# Calisma.net
KiCad netlist of a schematic drawn in Altium Designer
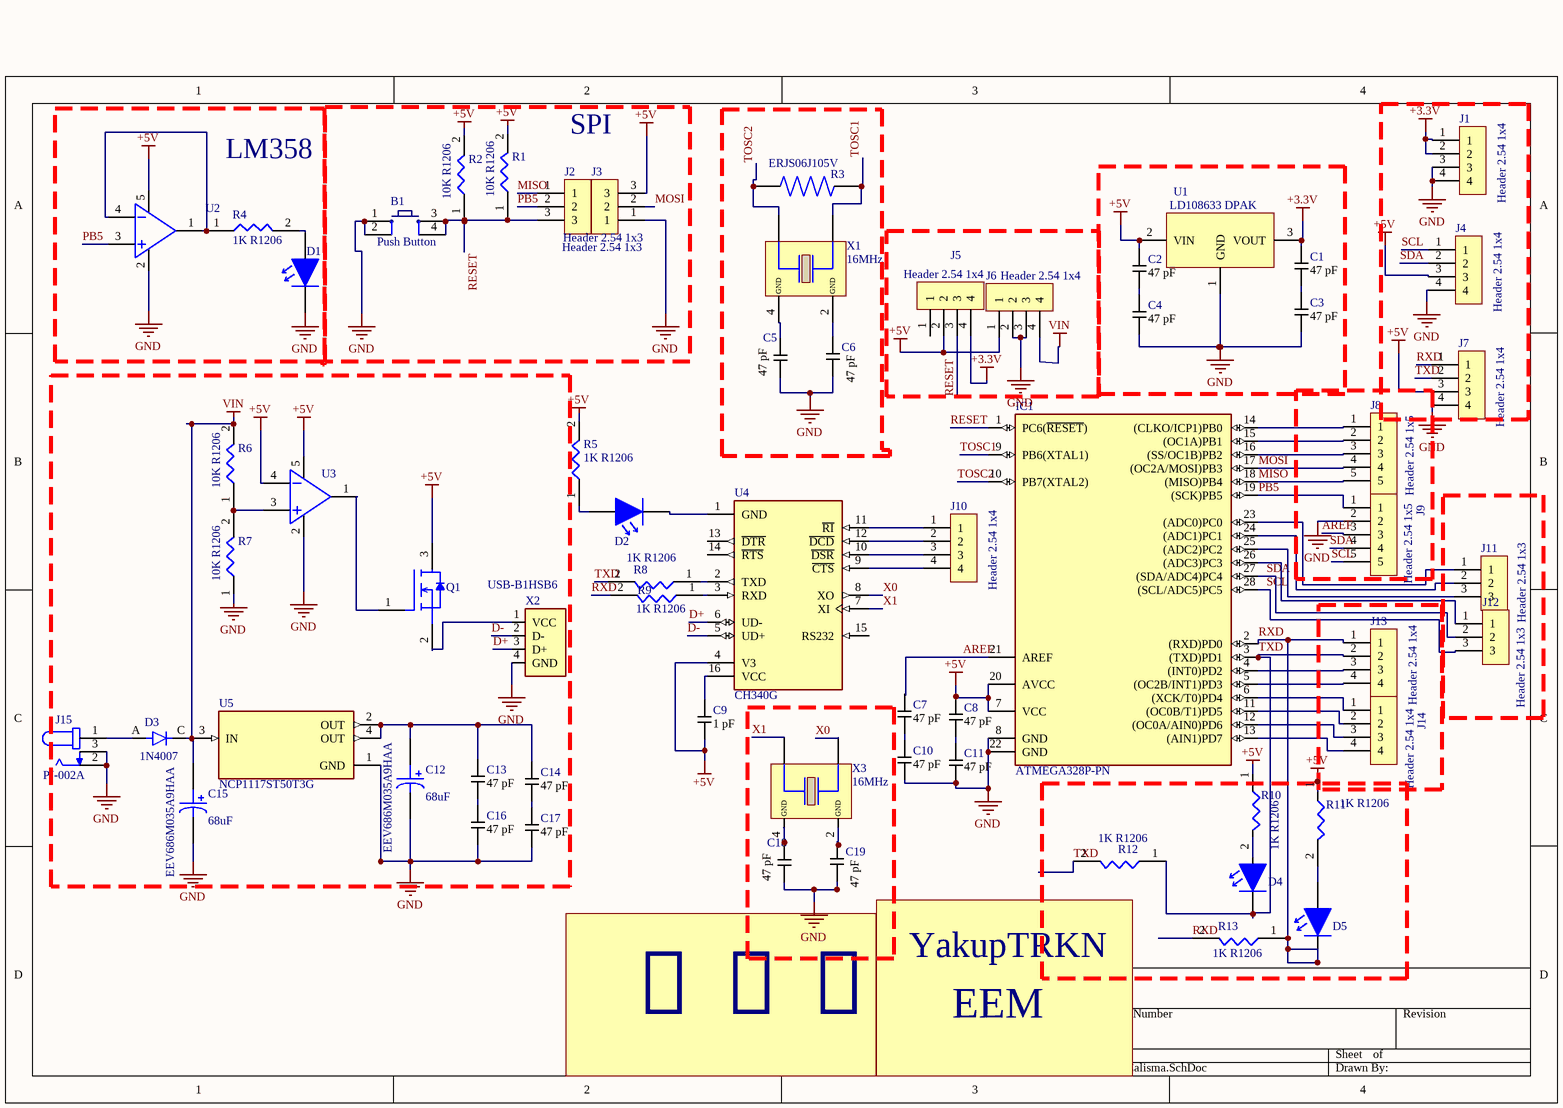
[diagram p0: Calisma.SchDoc]

(export (version "E")
  (design (tool "Eeschema 10.0.6"))
  (components
    (comp (ref "B1")
      (value "Push Button")
      (footprint "PUSB BUTTON-SMD")
      (description "Smd Push Button")
      (libsource (lib "Calisma") (part "Push Button"))
    )
    (comp (ref "C1")
      (value "CL10C470JB8NNNC")
      (footprint "SAMSUNG_CAP_0603_090")
      (description "CAP CER 47PF 50V C0G/NP0 0603")
      (fields (field (name "CAPACITANCE") "47 pF"))
      (libsource (lib "Calisma") (part "CL10C470JB8NNNC"))
    )
    (comp (ref "C2")
      (value "CL10C470JB8NNNC")
      (footprint "SAMSUNG_CAP_0603_090")
      (description "CAP CER 47PF 50V C0G/NP0 0603")
      (fields (field (name "CAPACITANCE") "47 pF"))
      (libsource (lib "Calisma") (part "CL10C470JB8NNNC"))
    )
    (comp (ref "C3")
      (value "CL10C470JB8NNNC")
      (footprint "SAMSUNG_CAP_0603_090")
      (description "CAP CER 47PF 50V C0G/NP0 0603")
      (fields (field (name "CAPACITANCE") "47 pF"))
      (libsource (lib "Calisma") (part "CL10C470JB8NNNC"))
    )
    (comp (ref "C4")
      (value "CL10C470JB8NNNC")
      (footprint "SAMSUNG_CAP_0603_090")
      (description "CAP CER 47PF 50V C0G/NP0 0603")
      (fields (field (name "CAPACITANCE") "47 pF"))
      (libsource (lib "Calisma") (part "CL10C470JB8NNNC"))
    )
    (comp (ref "C5")
      (value "CL10C470JB8NNNC")
      (footprint "SAMSUNG_CAP_0603_090")
      (description "CAP CER 47PF 50V C0G/NP0 0603")
      (fields (field (name "CAPACITANCE") "47 pF"))
      (libsource (lib "Calisma") (part "CL10C470JB8NNNC"))
    )
    (comp (ref "C6")
      (value "CL10C470JB8NNNC")
      (footprint "SAMSUNG_CAP_0603_090")
      (description "CAP CER 47PF 50V C0G/NP0 0603")
      (fields (field (name "CAPACITANCE") "47 pF"))
      (libsource (lib "Calisma") (part "CL10C470JB8NNNC"))
    )
    (comp (ref "C7")
      (value "CL10C470JB8NNNC")
      (footprint "SAMSUNG_CAP_0603_090")
      (description "CAP CER 47PF 50V C0G/NP0 0603")
      (fields (field (name "CAPACITANCE") "47 pF"))
      (libsource (lib "Calisma") (part "CL10C470JB8NNNC"))
    )
    (comp (ref "C8")
      (value "CL10C470JB8NNNC")
      (footprint "SAMSUNG_CAP_0603_090")
      (description "CAP CER 47PF 50V C0G/NP0 0603")
      (fields (field (name "CAPACITANCE") "47 pF"))
      (libsource (lib "Calisma") (part "CL10C470JB8NNNC"))
    )
    (comp (ref "C9")
      (value "CL10C010BB8NNNC")
      (footprint "SAMSUNG_CAP_0603_090")
      (description "CAP CER 1PF 50V C0G/NP0 0603")
      (fields (field (name "CAPACITANCE") "1 pF"))
      (libsource (lib "Calisma") (part "CL10C010BB8NNNC"))
    )
    (comp (ref "C10")
      (value "CL10C470JB8NNNC")
      (footprint "SAMSUNG_CAP_0603_090")
      (description "CAP CER 47PF 50V C0G/NP0 0603")
      (fields (field (name "CAPACITANCE") "47 pF"))
      (libsource (lib "Calisma") (part "CL10C470JB8NNNC"))
    )
    (comp (ref "C11")
      (value "CL10C470JB8NNNC")
      (footprint "SAMSUNG_CAP_0603_090")
      (description "CAP CER 47PF 50V C0G/NP0 0603")
      (fields (field (name "CAPACITANCE") "47 pF"))
      (libsource (lib "Calisma") (part "CL10C470JB8NNNC"))
    )
    (comp (ref "C12")
      (value "EEV686M035A9HAA")
      (footprint "CAP_EEVseries")
      (description "Cap Aluminum Lytic 68uF 35V 20% (6.3 X 7.7mm) SMD 280mA 2000h 105C T/R")
      (fields
        (field (name "MANUFACTURER") "KEMET")
        (field (name "TOLERANCE") "20%")
        (field (name "CAPACITANCE") "68uF")
      )
      (libsource (lib "Calisma") (part "CAP ALU 68uF"))
    )
    (comp (ref "C13")
      (value "CL10C470JB8NNNC")
      (footprint "SAMSUNG_CAP_0603_090")
      (description "CAP CER 47PF 50V C0G/NP0 0603")
      (fields (field (name "CAPACITANCE") "47 pF"))
      (libsource (lib "Calisma") (part "CL10C470JB8NNNC"))
    )
    (comp (ref "C14")
      (value "CL10C470JB8NNNC")
      (footprint "SAMSUNG_CAP_0603_090")
      (description "CAP CER 47PF 50V C0G/NP0 0603")
      (fields (field (name "CAPACITANCE") "47 pF"))
      (libsource (lib "Calisma") (part "CL10C470JB8NNNC"))
    )
    (comp (ref "C15")
      (value "EEV686M035A9HAA")
      (footprint "CAP_EEVseries")
      (description "Cap Aluminum Lytic 68uF 35V 20% (6.3 X 7.7mm) SMD 280mA 2000h 105C T/R")
      (fields
        (field (name "MANUFACTURER") "KEMET")
        (field (name "TOLERANCE") "20%")
        (field (name "CAPACITANCE") "68uF")
      )
      (libsource (lib "Calisma") (part "CAP ALU 68uF"))
    )
    (comp (ref "C16")
      (value "CL10C470JB8NNNC")
      (footprint "SAMSUNG_CAP_0603_090")
      (description "CAP CER 47PF 50V C0G/NP0 0603")
      (fields (field (name "CAPACITANCE") "47 pF"))
      (libsource (lib "Calisma") (part "CL10C470JB8NNNC"))
    )
    (comp (ref "C17")
      (value "CL10C470JB8NNNC")
      (footprint "SAMSUNG_CAP_0603_090")
      (description "CAP CER 47PF 50V C0G/NP0 0603")
      (fields (field (name "CAPACITANCE") "47 pF"))
      (libsource (lib "Calisma") (part "CL10C470JB8NNNC"))
    )
    (comp (ref "C18")
      (value "CL10C470JB8NNNC")
      (footprint "SAMSUNG_CAP_0603_090")
      (description "CAP CER 47PF 50V C0G/NP0 0603")
      (fields (field (name "CAPACITANCE") "47 pF"))
      (libsource (lib "Calisma") (part "CL10C470JB8NNNC"))
    )
    (comp (ref "C19")
      (value "CL10C470JB8NNNC")
      (footprint "SAMSUNG_CAP_0603_090")
      (description "CAP CER 47PF 50V C0G/NP0 0603")
      (fields (field (name "CAPACITANCE") "47 pF"))
      (libsource (lib "Calisma") (part "CL10C470JB8NNNC"))
    )
    (comp (ref "D1")
      (value "LH R974-LP-1")
      (footprint "LED_RED_0805")
      (description "LED Uni-Color Hyper Red 660nm 2-Pin Chip 0805(2012Metric) T/R")
      (fields (field (name "MANUFACTURER") "Osram Opto") (field (name "DESIGNED BY") "BERK"))
      (libsource (lib "Calisma") (part "LED RED 0805"))
    )
    (comp (ref "D2")
      (value "LTST-C171GKT")
      (footprint "LED_GREEN_0805")
      (description "Green 0805 130 º Min 5 mcd Typical 12 mcd Water Clear Lens SMT LED")
      (fields (field (name "MANUFACTURER") "Vishay Lite-On") (field (name "DESIGNED BY") "BERK"))
      (libsource (lib "Calisma") (part "LED GREEN 0805"))
    )
    (comp (ref "D3")
      (value "1N4007")
      (footprint "1N4007:DIOAD1060W80L520D270")
      (description "Diode Switching 1KV 1A 2-Pin DO-41")
      (fields (field (name "MF") "{'manufacturer': u'ON Semiconductor'}"))
      (libsource (lib "Calisma") (part "1N4007"))
    )
    (comp (ref "D4")
      (value "LTST-C171GKT")
      (footprint "LED_GREEN_0805")
      (description "Green 0805 130 º Min 5 mcd Typical 12 mcd Water Clear Lens SMT LED")
      (fields (field (name "MANUFACTURER") "Vishay Lite-On") (field (name "DESIGNED BY") "BERK"))
      (libsource (lib "Calisma") (part "LED GREEN 0805"))
    )
    (comp (ref "D5")
      (value "LTST-C171GKT")
      (footprint "LED_GREEN_0805")
      (description "Green 0805 130 º Min 5 mcd Typical 12 mcd Water Clear Lens SMT LED")
      (fields (field (name "MANUFACTURER") "Vishay Lite-On") (field (name "DESIGNED BY") "BERK"))
      (libsource (lib "Calisma") (part "LED GREEN 0805"))
    )
    (comp (ref "IC1")
      (value "ATMEGA328P-PN")
      (footprint "ATMEGA328P-PN:DIL28")
      (description "Atmel ATmega48/88/168/328 AVR Microcontroller")
      (fields (field (name "MF") "{'manufacturer': u'Microchip'}"))
      (libsource (lib "Calisma") (part "ATMEGA328P-PN"))
    )
    (comp (ref "J1")
      (value "Header 2.54 1x4")
      (footprint "Header 2.54 1x4")
      (libsource (lib "Calisma") (part "Header 2.54 1x4"))
    )
    (comp (ref "J2")
      (value "Header 2.54 1x3")
      (footprint "Header 2.54 1x3")
      (libsource (lib "") (part "Header 2.54 1x3_1"))
    )
    (comp (ref "J3")
      (value "Header 2.54 1x3")
      (footprint "Header 2.54 1x3")
      (libsource (lib "Calisma") (part "Header 2.54 1x3"))
    )
    (comp (ref "J4")
      (value "Header 2.54 1x4")
      (footprint "Header 2.54 1x4")
      (libsource (lib "Calisma") (part "Header 2.54 1x4"))
    )
    (comp (ref "J5")
      (value "Header 2.54 1x4")
      (footprint "Header 2.54 1x4")
      (libsource (lib "") (part "Header 2.54 1x4_1"))
    )
    (comp (ref "J6")
      (value "Header 2.54 1x4")
      (footprint "Header 2.54 1x4")
      (libsource (lib "") (part "Header 2.54 1x4_1"))
    )
    (comp (ref "J7")
      (value "Header 2.54 1x4")
      (footprint "Header 2.54 1x4")
      (libsource (lib "Calisma") (part "Header 2.54 1x4"))
    )
    (comp (ref "J8")
      (value "Header 2.54 1x5")
      (footprint "Header 2.54 1x5")
      (libsource (lib "Calisma") (part "Header 2.54 1x5"))
    )
    (comp (ref "J9")
      (value "Header 2.54 1x5")
      (footprint "Header 2.54 1x5")
      (libsource (lib "Calisma") (part "Header 2.54 1x5"))
    )
    (comp (ref "J10")
      (value "Header 2.54 1x4")
      (footprint "Header 2.54 1x4")
      (libsource (lib "Calisma") (part "Header 2.54 1x4"))
    )
    (comp (ref "J11")
      (value "Header 2.54 1x3")
      (footprint "Header 2.54 1x3")
      (libsource (lib "") (part "Header 2.54 1x3_1"))
    )
    (comp (ref "J12")
      (value "Header 2.54 1x3")
      (footprint "Header 2.54 1x3")
      (libsource (lib "") (part "Header 2.54 1x3_1"))
    )
    (comp (ref "J13")
      (value "Header 2.54 1x4")
      (footprint "Header 2.54 1x4")
      (libsource (lib "Calisma") (part "Header 2.54 1x4"))
    )
    (comp (ref "J14")
      (value "Header 2.54 1x4")
      (footprint "Header 2.54 1x4")
      (libsource (lib "Calisma") (part "Header 2.54 1x4"))
    )
    (comp (ref "J15")
      (value "PJ-002A")
      (footprint "PJ-002A:CUI_PJ-002A")
      (description "2.0 mm Center Pin, 2.5 A, Right Angle, Through Hole, Dc Power Jack Connector")
      (fields (field (name "MF") "{'manufacturer': u'CUI Devices'}"))
      (libsource (lib "Calisma") (part "PJ-002A"))
    )
    (comp (ref "Q1")
      (value "SSM3K357R,LF")
      (footprint "SOT-23F")
      (description "X34 SMALL LOW ON RESISTANCE MOSF")
      (fields (field (name "MANUFACTURER") "Toshiba") (field (name "DESIGNED BY") "BERK"))
      (libsource (lib "Calisma") (part "SSM3K357R,LF"))
    )
    (comp (ref "R1")
      (value "10K R1206")
      (footprint "R1206 Resıstor")
      (libsource (lib "Calisma") (part "10K R1206"))
    )
    (comp (ref "R2")
      (value "10K R1206")
      (footprint "R1206 Resıstor")
      (libsource (lib "Calisma") (part "10K R1206"))
    )
    (comp (ref "R3")
      (value "ERJS06J105V")
      (footprint "ERJ-S06J105V:RES_ERJS06J105V")
      (fields (field (name "MF") "{'manufacturer': u'Panasonic'}"))
      (libsource (lib "Calisma") (part "ERJS06J105V"))
    )
    (comp (ref "R4")
      (value "1K R1206")
      (footprint "R1206 Resıstor")
      (libsource (lib "Calisma") (part "1K R1206"))
    )
    (comp (ref "R5")
      (value "1K R1206")
      (footprint "R1206 Resıstor")
      (libsource (lib "Calisma") (part "1K R1206"))
    )
    (comp (ref "R6")
      (value "10K R1206")
      (footprint "R1206 Resıstor")
      (libsource (lib "Calisma") (part "10K R1206"))
    )
    (comp (ref "R7")
      (value "10K R1206")
      (footprint "R1206 Resıstor")
      (libsource (lib "Calisma") (part "10K R1206"))
    )
    (comp (ref "R8")
      (value "1K R1206")
      (footprint "R1206 Resıstor")
      (libsource (lib "Calisma") (part "1K R1206"))
    )
    (comp (ref "R9")
      (value "1K R1206")
      (footprint "R1206 Resıstor")
      (libsource (lib "Calisma") (part "1K R1206"))
    )
    (comp (ref "R10")
      (value "1K R1206")
      (footprint "R1206 Resıstor")
      (libsource (lib "Calisma") (part "1K R1206"))
    )
    (comp (ref "R11")
      (value "1K R1206")
      (footprint "R1206 Resıstor")
      (libsource (lib "Calisma") (part "1K R1206"))
    )
    (comp (ref "R12")
      (value "1K R1206")
      (footprint "R1206 Resıstor")
      (libsource (lib "Calisma") (part "1K R1206"))
    )
    (comp (ref "R13")
      (value "1K R1206")
      (footprint "R1206 Resıstor")
      (libsource (lib "Calisma") (part "1K R1206"))
    )
    (comp (ref "U1")
      (value "LD108633 DPAK")
      (footprint "DPAK228P972X230-3N")
      (description "LD1086 3.3V REGULATOR")
      (libsource (lib "Calisma") (part "LD108633 DPAK"))
    )
    (comp (ref "U2")
      (value "OPA314AIDBVR")
      (footprint "SOT23-5")
      (description "Op Amp OPA314")
      (fields (field (name "MANUFACTURER") "Texas Instruments") (field (name "DESIGNED BY") "BERK"))
      (libsource (lib "Calisma") (part "OPA314"))
    )
    (comp (ref "U3")
      (value "OPA314AIDBVR")
      (footprint "SOT23-5")
      (description "Op Amp OPA314")
      (fields (field (name "MANUFACTURER") "Texas Instruments") (field (name "DESIGNED BY") "BERK"))
      (libsource (lib "Calisma") (part "OPA314"))
    )
    (comp (ref "U4")
      (value "CH340G")
      (footprint "Ch340G:SOIC127P600X180-16N")
      (fields (field (name "MF") "{'manufacturer': u'WCH'}"))
      (libsource (lib "Calisma") (part "CH340G"))
    )
    (comp (ref "U5")
      (value "NCP1117ST50T3G")
      (footprint "NCP1117ST50T3G:SOT230P700X180-4N")
      (description "1.0 A Low-Dropout Positive ,Fixed and Adjustable,Voltage Regulators")
      (fields (field (name "MF") "{'manufacturer': u'ON Semiconductor'}"))
      (libsource (lib "Calisma") (part "NCP1117ST50T3G"))
    )
    (comp (ref "X1")
      (value "ECS-160-20-30B-TR")
      (footprint "ECS")
      (description "CRYSTAL 16.0000MHZ 20PF SMD")
      (fields
        (field (name "MANUFACTURER") "ECS International")
        (field (name "TOLERANCE") "50ppm")
        (field (name "FREQUENCY") "16MHz")
        (field (name "DESIGNED BY") "BERK")
      )
      (libsource (lib "Calisma") (part "CRYSTAL 16MHz"))
    )
    (comp (ref "X2")
      (value "USB-B1HSB6")
      (footprint "USB-B1HSB6:OST_USB-B1HSB6")
      (description "Conn Usb Type b r/a Black")
      (fields (field (name "MF") "{'manufacturer': u'On Shore'}"))
      (libsource (lib "Calisma") (part "USB-B1HSB6"))
    )
    (comp (ref "X3")
      (value "ECS-160-20-30B-TR")
      (footprint "ECS")
      (description "CRYSTAL 16.0000MHZ 20PF SMD")
      (fields
        (field (name "MANUFACTURER") "ECS International")
        (field (name "TOLERANCE") "50ppm")
        (field (name "FREQUENCY") "16MHz")
        (field (name "DESIGNED BY") "BERK")
      )
      (libsource (lib "Calisma") (part "CRYSTAL 16MHz"))
    )
  )
  (nets
    (net (code "1") (name "+3.3V") (class "Default")
      (node (ref "C1") (pin "2") (pinfunction "2_2") (pintype "passive"))
      (node (ref "J1") (pin "1") (pinfunction "1_1") (pintype "passive"))
      (node (ref "J1") (pin "2") (pinfunction "2_2") (pintype "passive"))
      (node (ref "J5") (pin "4") (pinfunction "4_4") (pintype "passive"))
      (node (ref "U1") (pin "3") (pinfunction "VOUT_3") (pintype "passive"))
    )
    (net (code "2") (name "+5V") (class "Default")
      (node (ref "C2") (pin "2") (pinfunction "2_2") (pintype "passive"))
      (node (ref "C8") (pin "2") (pinfunction "2_2") (pintype "passive"))
      (node (ref "C9") (pin "1") (pinfunction "1_1") (pintype "passive"))
      (node (ref "IC1") (pin "20") (pinfunction "AVCC_20") (pintype "power_in"))
      (node (ref "IC1") (pin "7") (pinfunction "VCC_7") (pintype "power_in"))
      (node (ref "J3") (pin "3") (pinfunction "3_3") (pintype "passive"))
      (node (ref "J4") (pin "3") (pinfunction "3_3") (pintype "passive"))
      (node (ref "J5") (pin "2") (pinfunction "2_2") (pintype "passive"))
      (node (ref "J6") (pin "1") (pinfunction "1_1") (pintype "passive"))
      (node (ref "J7") (pin "3") (pinfunction "3_3") (pintype "passive"))
      (node (ref "Q1") (pin "3") (pinfunction "D_3") (pintype "passive"))
      (node (ref "R1") (pin "2") (pinfunction "2_2") (pintype "passive"))
      (node (ref "R10") (pin "1") (pinfunction "1_1") (pintype "passive"))
      (node (ref "R11") (pin "1") (pinfunction "1_1") (pintype "passive"))
      (node (ref "R2") (pin "2") (pinfunction "2_2") (pintype "passive"))
      (node (ref "R5") (pin "2") (pinfunction "2_2") (pintype "passive"))
      (node (ref "U1") (pin "2") (pinfunction "VIN_2") (pintype "passive"))
      (node (ref "U2") (pin "5") (pinfunction "5_5") (pintype "passive"))
      (node (ref "U3") (pin "4") (pinfunction "4_4") (pintype "passive"))
      (node (ref "U3") (pin "5") (pinfunction "5_5") (pintype "passive"))
      (node (ref "U4") (pin "4") (pinfunction "V3_4") (pintype "power_in"))
    )
    (net (code "3") (name "/AREF") (class "Default")
      (node (ref "IC1") (pin "21") (pinfunction "AREF_21") (pintype "passive"))
      (node (ref "J9") (pin "3") (pinfunction "3_3") (pintype "passive"))
    )
    (net (code "4") (name "/D+") (class "Default")
      (node (ref "U4") (pin "6") (pinfunction "UD-_6") (pintype "bidirectional"))
      (node (ref "X2") (pin "3") (pinfunction "D+_3") (pintype "bidirectional"))
    )
    (net (code "5") (name "/D-") (class "Default")
      (node (ref "U4") (pin "5") (pinfunction "UD+_5") (pintype "bidirectional"))
      (node (ref "X2") (pin "2") (pinfunction "D-_2") (pintype "bidirectional"))
    )
    (net (code "6") (name "/MISO") (class "Default")
      (node (ref "IC1") (pin "18") (pinfunction "(MISO)PB4_18") (pintype "bidirectional"))
      (node (ref "J2") (pin "1") (pinfunction "1_1") (pintype "passive"))
      (node (ref "J8") (pin "5") (pinfunction "5_5") (pintype "passive"))
    )
    (net (code "7") (name "/MOSI") (class "Default")
      (node (ref "IC1") (pin "17") (pinfunction "(OC2A/MOSI)PB3_17") (pintype "bidirectional"))
      (node (ref "J3") (pin "2") (pinfunction "2_2") (pintype "passive"))
      (node (ref "J8") (pin "4") (pinfunction "4_4") (pintype "passive"))
    )
    (net (code "8") (name "/PB5") (class "Default")
      (node (ref "IC1") (pin "19") (pinfunction "(SCK)PB5_19") (pintype "bidirectional"))
      (node (ref "J2") (pin "2") (pinfunction "2_2") (pintype "passive"))
      (node (ref "J9") (pin "1") (pinfunction "1_1") (pintype "passive"))
      (node (ref "U2") (pin "3") (pinfunction "3_3") (pintype "passive"))
    )
    (net (code "9") (name "/RESET") (class "Default")
      (node (ref "B1") (pin "3") (pinfunction "3_3") (pintype "passive"))
      (node (ref "B1") (pin "4") (pinfunction "4_4") (pintype "passive"))
      (node (ref "IC1") (pin "1") (pinfunction "PC6(~{RESET})_1") (pintype "bidirectional"))
      (node (ref "J2") (pin "3") (pinfunction "3_3") (pintype "passive"))
      (node (ref "J5") (pin "3") (pinfunction "3_3") (pintype "passive"))
      (node (ref "R1") (pin "1") (pinfunction "1_1") (pintype "passive"))
      (node (ref "R2") (pin "1") (pinfunction "1_1") (pintype "passive"))
    )
    (net (code "10") (name "/RXD") (class "Default")
      (node (ref "D5") (pin "1") (pinfunction "1_1") (pintype "power_in"))
      (node (ref "IC1") (pin "2") (pinfunction "(RXD)PD0_2") (pintype "bidirectional"))
      (node (ref "J13") (pin "1") (pinfunction "1_1") (pintype "passive"))
      (node (ref "J7") (pin "1") (pinfunction "1_1") (pintype "passive"))
      (node (ref "R13") (pin "1") (pinfunction "1_1") (pintype "passive"))
      (node (ref "R13") (pin "2") (pinfunction "2_2") (pintype "passive"))
      (node (ref "R9") (pin "2") (pinfunction "2_2") (pintype "passive"))
    )
    (net (code "11") (name "/SCL") (class "Default")
      (node (ref "IC1") (pin "28") (pinfunction "(SCL/ADC5)PC5_28") (pintype "bidirectional"))
      (node (ref "J12") (pin "3") (pinfunction "3_3") (pintype "passive"))
      (node (ref "J4") (pin "1") (pinfunction "1_1") (pintype "passive"))
      (node (ref "J9") (pin "5") (pinfunction "5_5") (pintype "passive"))
    )
    (net (code "12") (name "/SDA") (class "Default")
      (node (ref "IC1") (pin "27") (pinfunction "(SDA/ADC4)PC4_27") (pintype "bidirectional"))
      (node (ref "J12") (pin "2") (pinfunction "2_2") (pintype "passive"))
      (node (ref "J4") (pin "2") (pinfunction "2_2") (pintype "passive"))
      (node (ref "J9") (pin "4") (pinfunction "4_4") (pintype "passive"))
    )
    (net (code "13") (name "/TOSC1") (class "Default")
      (node (ref "IC1") (pin "9") (pinfunction "PB6(XTAL1)_9") (pintype "bidirectional"))
      (node (ref "R3") (pin "2") (pinfunction "2_2") (pintype "passive"))
      (node (ref "X1") (pin "1") (pinfunction "1_1") (pintype "passive"))
    )
    (net (code "14") (name "/TOSC2") (class "Default")
      (node (ref "IC1") (pin "10") (pinfunction "PB7(XTAL2)_10") (pintype "bidirectional"))
      (node (ref "R3") (pin "1") (pinfunction "1_1") (pintype "passive"))
      (node (ref "X1") (pin "3") (pinfunction "3_3") (pintype "passive"))
    )
    (net (code "15") (name "/TXD") (class "Default")
      (node (ref "D4") (pin "1") (pinfunction "1_1") (pintype "power_in"))
      (node (ref "IC1") (pin "3") (pinfunction "(TXD)PD1_3") (pintype "bidirectional"))
      (node (ref "J13") (pin "2") (pinfunction "2_2") (pintype "passive"))
      (node (ref "J7") (pin "2") (pinfunction "2_2") (pintype "passive"))
      (node (ref "R12") (pin "1") (pinfunction "1_1") (pintype "passive"))
      (node (ref "R12") (pin "2") (pinfunction "2_2") (pintype "passive"))
      (node (ref "R8") (pin "2") (pinfunction "2_2") (pintype "passive"))
    )
    (net (code "16") (name "/X0") (class "Default")
      (node (ref "U4") (pin "8") (pinfunction "XO_8") (pintype "output"))
      (node (ref "X3") (pin "1") (pinfunction "1_1") (pintype "passive"))
    )
    (net (code "17") (name "/X1") (class "Default")
      (node (ref "U4") (pin "7") (pinfunction "XI_7") (pintype "input"))
      (node (ref "X3") (pin "3") (pinfunction "3_3") (pintype "passive"))
    )
    (net (code "18") (name "GND") (class "Default")
      (node (ref "B1") (pin "1") (pinfunction "1_1") (pintype "passive"))
      (node (ref "B1") (pin "2") (pinfunction "2_2") (pintype "passive"))
      (node (ref "C10") (pin "1") (pinfunction "1_1") (pintype "passive"))
      (node (ref "C11") (pin "1") (pinfunction "1_1") (pintype "passive"))
      (node (ref "C12") (pin "2") (pinfunction "2_2") (pintype "passive"))
      (node (ref "C15") (pin "2") (pinfunction "2_2") (pintype "passive"))
      (node (ref "C16") (pin "1") (pinfunction "1_1") (pintype "passive"))
      (node (ref "C17") (pin "1") (pinfunction "1_1") (pintype "passive"))
      (node (ref "C18") (pin "1") (pinfunction "1_1") (pintype "passive"))
      (node (ref "C19") (pin "1") (pinfunction "1_1") (pintype "passive"))
      (node (ref "C3") (pin "1") (pinfunction "1_1") (pintype "passive"))
      (node (ref "C4") (pin "1") (pinfunction "1_1") (pintype "passive"))
      (node (ref "C5") (pin "1") (pinfunction "1_1") (pintype "passive"))
      (node (ref "C6") (pin "1") (pinfunction "1_1") (pintype "passive"))
      (node (ref "D1") (pin "1") (pinfunction "1_1") (pintype "power_in"))
      (node (ref "IC1") (pin "22") (pinfunction "GND_22") (pintype "power_in"))
      (node (ref "IC1") (pin "8") (pinfunction "GND_8") (pintype "power_in"))
      (node (ref "J1") (pin "3") (pinfunction "3_3") (pintype "passive"))
      (node (ref "J1") (pin "4") (pinfunction "4_4") (pintype "passive"))
      (node (ref "J15") (pin "2") (pinfunction "2_2") (pintype "passive"))
      (node (ref "J15") (pin "3") (pinfunction "3_3") (pintype "passive"))
      (node (ref "J3") (pin "1") (pinfunction "1_1") (pintype "passive"))
      (node (ref "J4") (pin "4") (pinfunction "4_4") (pintype "passive"))
      (node (ref "J6") (pin "2") (pinfunction "2_2") (pintype "passive"))
      (node (ref "J6") (pin "3") (pinfunction "3_3") (pintype "passive"))
      (node (ref "J7") (pin "4") (pinfunction "4_4") (pintype "passive"))
      (node (ref "J9") (pin "2") (pinfunction "2_2") (pintype "passive"))
      (node (ref "R7") (pin "1") (pinfunction "1_1") (pintype "passive"))
      (node (ref "U1") (pin "1") (pinfunction "GND_1") (pintype "passive"))
      (node (ref "U2") (pin "2") (pinfunction "2_2") (pintype "passive"))
      (node (ref "U3") (pin "2") (pinfunction "2_2") (pintype "passive"))
      (node (ref "U5") (pin "1") (pinfunction "GND_1") (pintype "power_in"))
      (node (ref "X2") (pin "4") (pinfunction "GND_4") (pintype "power_in"))
    )
    (net (code "19") (name "Net-(C1-Pad1)") (class "Default")
      (node (ref "C1") (pin "1") (pinfunction "1_1") (pintype "passive"))
      (node (ref "C3") (pin "2") (pinfunction "2_2") (pintype "passive"))
    )
    (net (code "20") (name "Net-(C2-Pad1)") (class "Default")
      (node (ref "C2") (pin "1") (pinfunction "1_1") (pintype "passive"))
      (node (ref "C4") (pin "2") (pinfunction "2_2") (pintype "passive"))
    )
    (net (code "21") (name "Net-(C5-Pad2)") (class "Default")
      (node (ref "C5") (pin "2") (pinfunction "2_2") (pintype "passive"))
      (node (ref "X1") (pin "4") (pinfunction "GND_4") (pintype "passive"))
    )
    (net (code "22") (name "Net-(C6-Pad2)") (class "Default")
      (node (ref "C6") (pin "2") (pinfunction "2_2") (pintype "passive"))
      (node (ref "X1") (pin "2") (pinfunction "GND_2") (pintype "passive"))
    )
    (net (code "23") (name "Net-(C10-Pad2)") (class "Default")
      (node (ref "C10") (pin "2") (pinfunction "2_2") (pintype "passive"))
      (node (ref "C7") (pin "1") (pinfunction "1_1") (pintype "passive"))
    )
    (net (code "24") (name "Net-(C11-Pad2)") (class "Default")
      (node (ref "C11") (pin "2") (pinfunction "2_2") (pintype "passive"))
      (node (ref "C8") (pin "1") (pinfunction "1_1") (pintype "passive"))
    )
    (net (code "25") (name "Net-(C12-Pad1)") (class "Default")
      (node (ref "C12") (pin "1") (pinfunction "1_1") (pintype "passive"))
      (node (ref "C13") (pin "2") (pinfunction "2_2") (pintype "passive"))
      (node (ref "C14") (pin "2") (pinfunction "2_2") (pintype "passive"))
      (node (ref "U5") (pin "2") (pinfunction "OUT_2") (pintype "output"))
      (node (ref "U5") (pin "4") (pinfunction "OUT_4") (pintype "output"))
    )
    (net (code "26") (name "Net-(C13-Pad1)") (class "Default")
      (node (ref "C13") (pin "1") (pinfunction "1_1") (pintype "passive"))
      (node (ref "C16") (pin "2") (pinfunction "2_2") (pintype "passive"))
    )
    (net (code "27") (name "Net-(C14-Pad1)") (class "Default")
      (node (ref "C14") (pin "1") (pinfunction "1_1") (pintype "passive"))
      (node (ref "C17") (pin "2") (pinfunction "2_2") (pintype "passive"))
    )
    (net (code "28") (name "Net-(C18-Pad2)") (class "Default")
      (node (ref "C18") (pin "2") (pinfunction "2_2") (pintype "passive"))
      (node (ref "X3") (pin "4") (pinfunction "GND_4") (pintype "passive"))
    )
    (net (code "29") (name "Net-(C19-Pad2)") (class "Default")
      (node (ref "C19") (pin "2") (pinfunction "2_2") (pintype "passive"))
      (node (ref "X3") (pin "2") (pinfunction "GND_2") (pintype "passive"))
    )
    (net (code "30") (name "Net-(D1-Pad2)") (class "Default")
      (node (ref "D1") (pin "2") (pinfunction "2_2") (pintype "power_in"))
      (node (ref "R4") (pin "2") (pinfunction "2_2") (pintype "passive"))
    )
    (net (code "31") (name "Net-(D2-Pad2)") (class "Default")
      (node (ref "D2") (pin "2") (pinfunction "2_2") (pintype "power_in"))
      (node (ref "R5") (pin "1") (pinfunction "1_1") (pintype "passive"))
    )
    (net (code "32") (name "Net-(D3-PadA)") (class "Default")
      (node (ref "D3") (pin "A") (pinfunction "A_A") (pintype "passive"))
      (node (ref "J15") (pin "1") (pinfunction "1_1") (pintype "passive"))
    )
    (net (code "33") (name "Net-(D4-Pad2)") (class "Default")
      (node (ref "D4") (pin "2") (pinfunction "2_2") (pintype "power_in"))
      (node (ref "R10") (pin "2") (pinfunction "2_2") (pintype "passive"))
    )
    (net (code "34") (name "Net-(D5-Pad2)") (class "Default")
      (node (ref "D5") (pin "2") (pinfunction "2_2") (pintype "power_in"))
      (node (ref "R11") (pin "2") (pinfunction "2_2") (pintype "passive"))
    )
    (net (code "35") (name "Net-(IC1-(ADC0)PC0)") (class "Default")
      (node (ref "IC1") (pin "23") (pinfunction "(ADC0)PC0_23") (pintype "bidirectional"))
      (node (ref "J11") (pin "1") (pinfunction "1_1") (pintype "passive"))
    )
    (net (code "36") (name "Net-(IC1-(ADC1)PC1)") (class "Default")
      (node (ref "IC1") (pin "24") (pinfunction "(ADC1)PC1_24") (pintype "bidirectional"))
      (node (ref "J11") (pin "2") (pinfunction "2_2") (pintype "passive"))
    )
    (net (code "37") (name "Net-(IC1-(ADC2)PC2)") (class "Default")
      (node (ref "IC1") (pin "25") (pinfunction "(ADC2)PC2_25") (pintype "bidirectional"))
      (node (ref "J11") (pin "3") (pinfunction "3_3") (pintype "passive"))
    )
    (net (code "38") (name "Net-(IC1-(ADC3)PC3)") (class "Default")
      (node (ref "IC1") (pin "26") (pinfunction "(ADC3)PC3_26") (pintype "bidirectional"))
      (node (ref "J12") (pin "1") (pinfunction "1_1") (pintype "passive"))
    )
    (net (code "39") (name "Net-(IC1-(AIN1)PD7)") (class "Default")
      (node (ref "IC1") (pin "13") (pinfunction "(AIN1)PD7_13") (pintype "bidirectional"))
      (node (ref "J14") (pin "4") (pinfunction "4_4") (pintype "passive"))
    )
    (net (code "40") (name "Net-(IC1-(CLKO{slash}ICP1)PB0)") (class "Default")
      (node (ref "IC1") (pin "14") (pinfunction "(CLKO/ICP1)PB0_14") (pintype "bidirectional"))
      (node (ref "J8") (pin "1") (pinfunction "1_1") (pintype "passive"))
    )
    (net (code "41") (name "Net-(IC1-(INT0)PD2)") (class "Default")
      (node (ref "IC1") (pin "4") (pinfunction "(INT0)PD2_4") (pintype "bidirectional"))
      (node (ref "J13") (pin "3") (pinfunction "3_3") (pintype "passive"))
    )
    (net (code "42") (name "Net-(IC1-(OC0A{slash}AIN0)PD6)") (class "Default")
      (node (ref "IC1") (pin "12") (pinfunction "(OC0A/AIN0)PD6_12") (pintype "bidirectional"))
      (node (ref "J14") (pin "3") (pinfunction "3_3") (pintype "passive"))
    )
    (net (code "43") (name "Net-(IC1-(OC0B{slash}T1)PD5)") (class "Default")
      (node (ref "IC1") (pin "11") (pinfunction "(OC0B/T1)PD5_11") (pintype "bidirectional"))
      (node (ref "J14") (pin "2") (pinfunction "2_2") (pintype "passive"))
    )
    (net (code "44") (name "Net-(IC1-(OC1A)PB1)") (class "Default")
      (node (ref "IC1") (pin "15") (pinfunction "(OC1A)PB1_15") (pintype "bidirectional"))
      (node (ref "J8") (pin "2") (pinfunction "2_2") (pintype "passive"))
    )
    (net (code "45") (name "Net-(IC1-(OC2B{slash}INT1)PD3)") (class "Default")
      (node (ref "IC1") (pin "5") (pinfunction "(OC2B/INT1)PD3_5") (pintype "bidirectional"))
      (node (ref "J13") (pin "4") (pinfunction "4_4") (pintype "passive"))
    )
    (net (code "46") (name "Net-(IC1-(SS{slash}OC1B)PB2)") (class "Default")
      (node (ref "IC1") (pin "16") (pinfunction "(SS/OC1B)PB2_16") (pintype "bidirectional"))
      (node (ref "J8") (pin "3") (pinfunction "3_3") (pintype "passive"))
    )
    (net (code "47") (name "Net-(IC1-(XCK{slash}T0)PD4)") (class "Default")
      (node (ref "IC1") (pin "6") (pinfunction "(XCK/T0)PD4_6") (pintype "bidirectional"))
      (node (ref "J14") (pin "1") (pinfunction "1_1") (pintype "passive"))
    )
    (net (code "48") (name "Net-(Q1-G)") (class "Default")
      (node (ref "Q1") (pin "1") (pinfunction "G_1") (pintype "passive"))
      (node (ref "U3") (pin "1") (pinfunction "1_1") (pintype "passive"))
    )
    (net (code "49") (name "Net-(Q1-S)") (class "Default")
      (node (ref "Q1") (pin "2") (pinfunction "S_2") (pintype "passive"))
      (node (ref "X2") (pin "1") (pinfunction "VCC_1") (pintype "power_in"))
    )
    (net (code "50") (name "Net-(R4-Pad1)") (class "Default")
      (node (ref "R4") (pin "1") (pinfunction "1_1") (pintype "passive"))
      (node (ref "U2") (pin "1") (pinfunction "1_1") (pintype "passive"))
      (node (ref "U2") (pin "4") (pinfunction "4_4") (pintype "passive"))
    )
    (net (code "51") (name "Net-(R6-Pad1)") (class "Default")
      (node (ref "R6") (pin "1") (pinfunction "1_1") (pintype "passive"))
      (node (ref "R7") (pin "2") (pinfunction "2_2") (pintype "passive"))
      (node (ref "U3") (pin "3") (pinfunction "3_3") (pintype "passive"))
    )
    (net (code "52") (name "Net-(U4-GND)") (class "Default")
      (node (ref "D2") (pin "1") (pinfunction "1_1") (pintype "power_in"))
      (node (ref "U4") (pin "1") (pinfunction "GND_1") (pintype "power_in"))
    )
    (net (code "53") (name "Net-(U4-RXD)") (class "Default")
      (node (ref "R9") (pin "1") (pinfunction "1_1") (pintype "passive"))
      (node (ref "U4") (pin "3") (pinfunction "RXD_3") (pintype "input"))
    )
    (net (code "54") (name "Net-(U4-TXD)") (class "Default")
      (node (ref "R8") (pin "1") (pinfunction "1_1") (pintype "passive"))
      (node (ref "U4") (pin "2") (pinfunction "TXD_2") (pintype "output"))
    )
    (net (code "55") (name "Net-(U4-VCC)") (class "Default")
      (node (ref "C9") (pin "2") (pinfunction "2_2") (pintype "passive"))
      (node (ref "U4") (pin "16") (pinfunction "VCC_16") (pintype "power_in"))
    )
    (net (code "56") (name "Net-(U4-~{CTS})") (class "Default")
      (node (ref "J10") (pin "4") (pinfunction "4_4") (pintype "passive"))
      (node (ref "U4") (pin "9") (pinfunction "~{CTS}_9") (pintype "input"))
    )
    (net (code "57") (name "Net-(U4-~{DCD})") (class "Default")
      (node (ref "J10") (pin "2") (pinfunction "2_2") (pintype "passive"))
      (node (ref "U4") (pin "12") (pinfunction "~{DCD}_12") (pintype "input"))
    )
    (net (code "58") (name "Net-(U4-~{DSR})") (class "Default")
      (node (ref "J10") (pin "3") (pinfunction "3_3") (pintype "passive"))
      (node (ref "U4") (pin "10") (pinfunction "~{DSR}_10") (pintype "input"))
    )
    (net (code "59") (name "Net-(U4-~{RI})") (class "Default")
      (node (ref "J10") (pin "1") (pinfunction "1_1") (pintype "passive"))
      (node (ref "U4") (pin "11") (pinfunction "~{RI}_11") (pintype "input"))
    )
    (net (code "60") (name "VIN") (class "Default")
      (node (ref "C15") (pin "1") (pinfunction "1_1") (pintype "passive"))
      (node (ref "D3") (pin "C") (pinfunction "C_C") (pintype "passive"))
      (node (ref "J6") (pin "4") (pinfunction "4_4") (pintype "passive"))
      (node (ref "R6") (pin "2") (pinfunction "2_2") (pintype "passive"))
      (node (ref "U5") (pin "3") (pinfunction "IN_3") (pintype "input"))
    )
    (net (code "61") (name "unconnected-(C7-Pad2)") (class "Default")
      (node (ref "C7") (pin "2") (pinfunction "2_2") (pintype "passive"))
    )
    (net (code "62") (name "unconnected-(J5-Pad1)") (class "Default")
      (node (ref "J5") (pin "1") (pinfunction "1_1") (pintype "passive"))
    )
    (net (code "63") (name "unconnected-(U4-RS232-Pad15)") (class "Default")
      (node (ref "U4") (pin "15") (pinfunction "RS232_15") (pintype "input"))
    )
    (net (code "64") (name "unconnected-(U4-~{DTR}-Pad13)") (class "Default")
      (node (ref "U4") (pin "13") (pinfunction "~{DTR}_13") (pintype "output"))
    )
    (net (code "65") (name "unconnected-(U4-~{RTS}-Pad14)") (class "Default")
      (node (ref "U4") (pin "14") (pinfunction "~{RTS}_14") (pintype "output"))
    )
  )
)
